# NextOne_R2.net
KiCad netlist of a schematic drawn in EAGLE
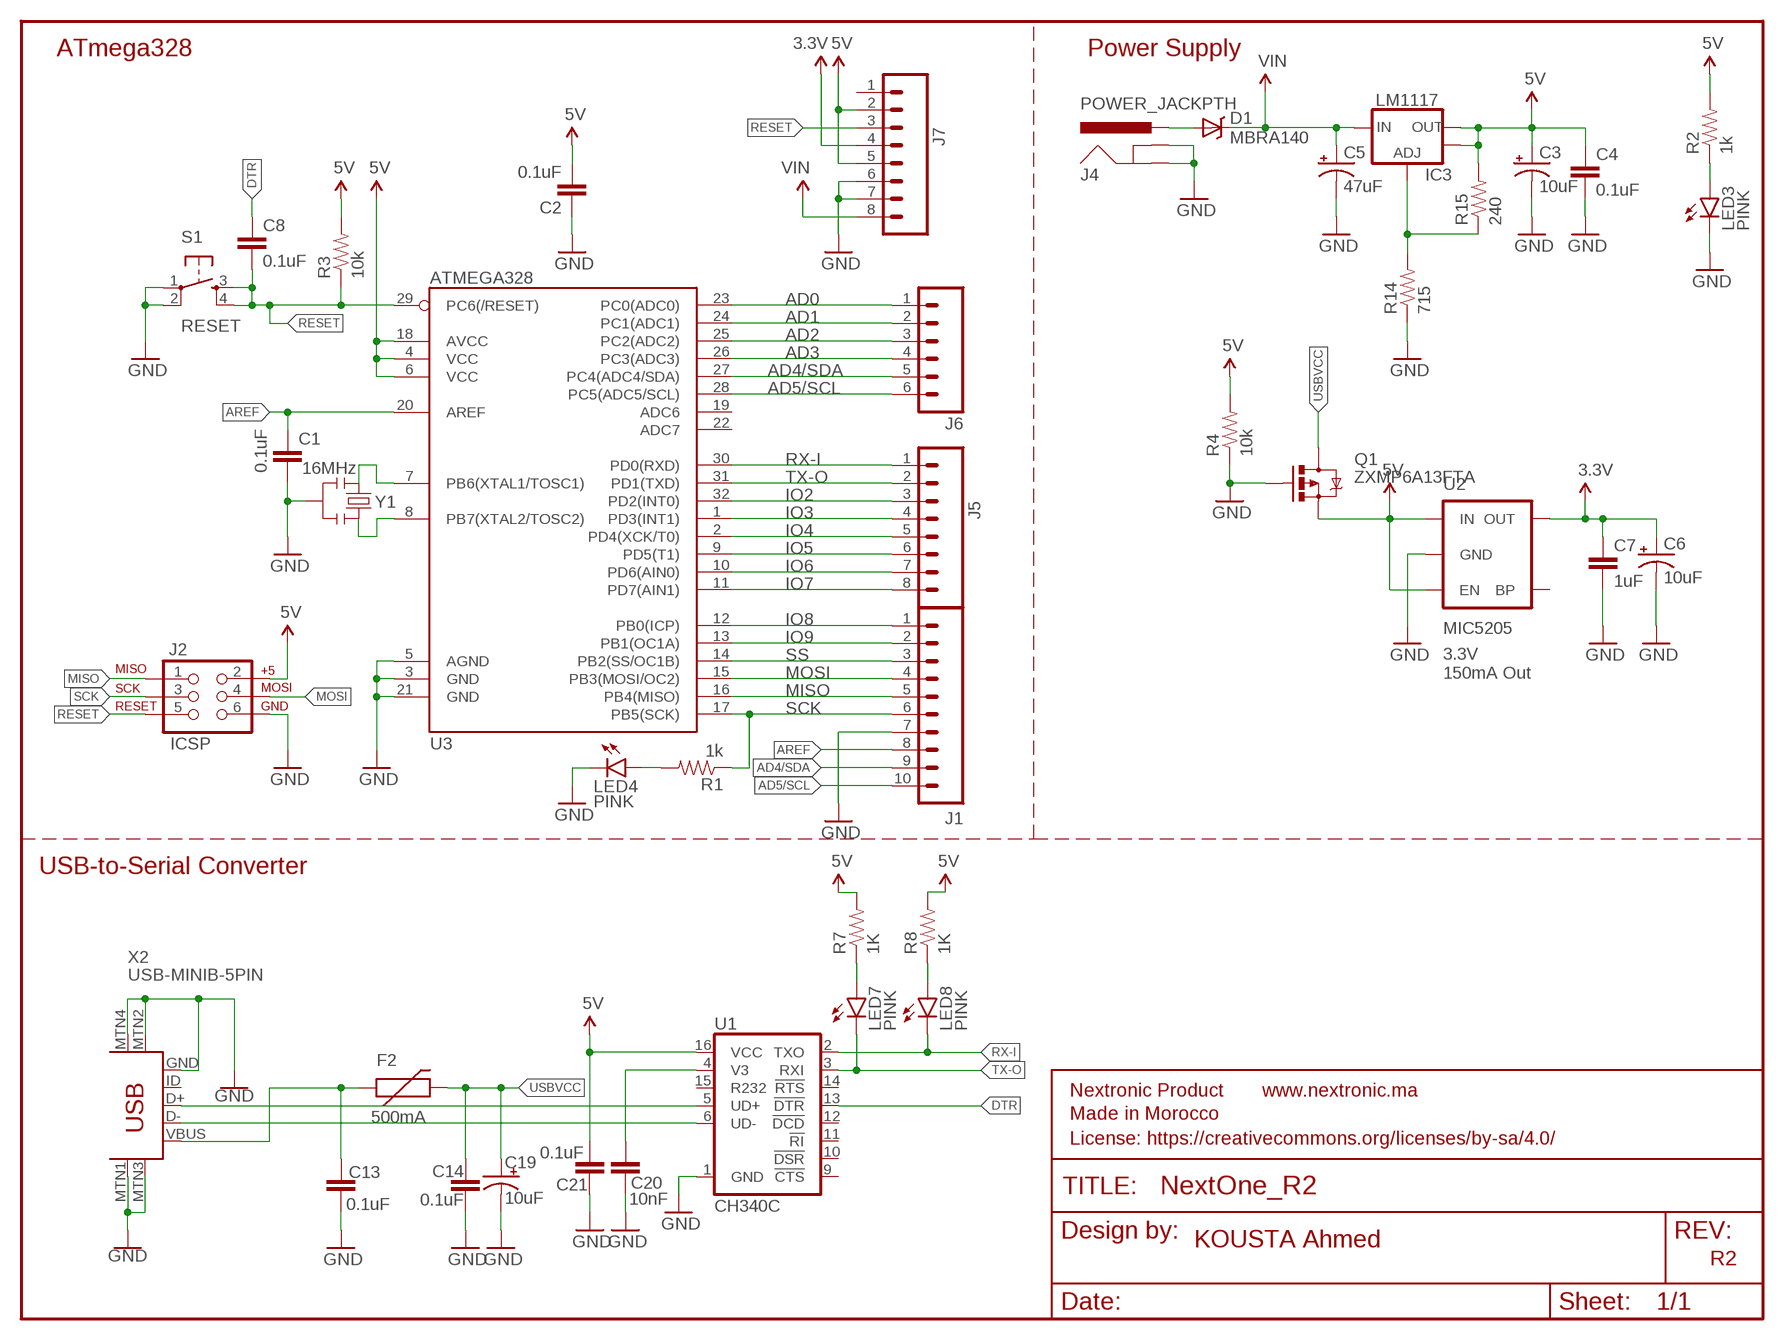
[diagram p0: schematic, sheet 1]

(export (version "E")
  (design (tool "Eeschema 10.0.6"))
  (components
    (comp (ref "C1")
      (value "0.1uF")
      (footprint "eagle-import:0603-CAP")
      (libsource (lib "eagle-import") (part "CAP0603-CAP"))
    )
    (comp (ref "C2")
      (value "0.1uF")
      (footprint "eagle-import:0603-CAP")
      (libsource (lib "eagle-import") (part "CAP0603-CAP"))
    )
    (comp (ref "C3")
      (value "10uF")
      (footprint "eagle-import:EIA3216")
      (libsource (lib "eagle-import") (part "CAP_POL1206"))
    )
    (comp (ref "C4")
      (value "0.1uF")
      (footprint "eagle-import:0603-CAP")
      (libsource (lib "eagle-import") (part "CAP0603-CAP"))
    )
    (comp (ref "C5")
      (value "47uF")
      (footprint "eagle-import:PANASONIC_D")
      (fields (field (name "MF") "PANASONIC ELECTRONIC COMPONENTS") (field (name "MPN") "EEE1CA470SP"))
      (libsource (lib "eagle-import") (part "CAP_POLD"))
    )
    (comp (ref "C6")
      (value "10uF")
      (footprint "eagle-import:EIA3216")
      (libsource (lib "eagle-import") (part "CAP_POL1206"))
    )
    (comp (ref "C7")
      (value "1uF")
      (footprint "eagle-import:0603-CAP")
      (fields (field (name "MF") "WALSIN") (field (name "MPN") "0805B104K500CT"))
      (libsource (lib "eagle-import") (part "CAP0603-CAP"))
    )
    (comp (ref "C8")
      (value "0.1uF")
      (footprint "eagle-import:0603-CAP")
      (libsource (lib "eagle-import") (part "CAP0603-CAP"))
    )
    (comp (ref "C13")
      (value "0.1uF")
      (footprint "eagle-import:0603")
      (libsource (lib "eagle-import") (part "0.1UF-0603-25V-(+80/-20%)"))
    )
    (comp (ref "C14")
      (value "0.1uF")
      (footprint "eagle-import:0603")
      (libsource (lib "eagle-import") (part "0.1UF-0603-25V-(+80/-20%)"))
    )
    (comp (ref "C19")
      (value "10uF")
      (footprint "eagle-import:EIA3216")
      (libsource (lib "eagle-import") (part "10UF-POLAR-EIA3216-16V-10%(TANT)"))
    )
    (comp (ref "C20")
      (value "10nF")
      (footprint "eagle-import:0603")
      (libsource (lib "eagle-import") (part "10NF-0603-50V-10%"))
    )
    (comp (ref "C21")
      (value "0.1uF")
      (footprint "eagle-import:0603")
      (libsource (lib "eagle-import") (part "0.1UF-0603-25V-(+80/-20%)"))
    )
    (comp (ref "D1")
      (value "MBRA140")
      (footprint "eagle-import:SMA-DIODE")
      (fields (field (name "MF") "DIODES INC.") (field (name "MPN") "B140-13-F"))
      (libsource (lib "eagle-import") (part "DIODE-SCHOTTKY_"))
    )
    (comp (ref "F2")
      (value "500mA")
      (footprint "eagle-import:PTC-1206")
      (libsource (lib "eagle-import") (part "PTCSMD"))
    )
    (comp (ref "FRAME1")
      (value "FRAME-LETTER")
      (footprint "eagle-import:CREATIVE_COMMONS")
      (fields (field (name "OC_FARNELL") "unknown"))
      (libsource (lib "eagle-import") (part "FRAME-LETTER"))
    )
    (comp (ref "IC3")
      (value "LM1117")
      (footprint "eagle-import:SOT223-ALT1")
      (fields (field (name "MF") "STMICROELECTRONICS") (field (name "MPN") "LD1117S33TR"))
      (libsource (lib "eagle-import") (part "V_REG_LM1117ALT1"))
    )
    (comp (ref "J1")
      (value "M10SILK_FEMALE_PTH")
      (footprint "eagle-import:1X10")
      (libsource (lib "eagle-import") (part "M10SILK_FEMALE_PTH"))
    )
    (comp (ref "J2")
      (value "ICSP")
      (footprint "eagle-import:2X3")
      (libsource (lib "eagle-import") (part "AVR_SPI_PRG_6PTH"))
    )
    (comp (ref "J4")
      (value "POWER_JACKPTH")
      (footprint "eagle-import:POWER_JACK_PTH")
      (libsource (lib "eagle-import") (part "POWER_JACKPTH"))
    )
    (comp (ref "J5")
      (value "M08")
      (footprint "eagle-import:1X08_ROUND")
      (libsource (lib "eagle-import") (part "M08"))
    )
    (comp (ref "J6")
      (value "M06SILK_FEMALE_PTH")
      (footprint "eagle-import:1X06")
      (libsource (lib "eagle-import") (part "M06SILK_FEMALE_PTH"))
    )
    (comp (ref "J7")
      (value "M08")
      (footprint "eagle-import:1X08_ROUND")
      (libsource (lib "eagle-import") (part "M08"))
    )
    (comp (ref "LED3")
      (value "PINK")
      (footprint "eagle-import:LED-1206@1")
      (libsource (lib "eagle-import") (part "LED-PINK1206"))
    )
    (comp (ref "LED4")
      (value "PINK")
      (footprint "eagle-import:LED-1206@1")
      (libsource (lib "eagle-import") (part "LED-PINK1206"))
    )
    (comp (ref "LED7")
      (value "PINK")
      (footprint "eagle-import:LED-1206@1")
      (libsource (lib "eagle-import") (part "LED-PINK1206"))
    )
    (comp (ref "LED8")
      (value "PINK")
      (footprint "eagle-import:LED-1206@1")
      (libsource (lib "eagle-import") (part "LED-PINK1206"))
    )
    (comp (ref "Q1")
      (value "ZXMP6A13FTA")
      (footprint "eagle-import:SOT23-3")
      (fields (field (name "MF") "DIODES INC."))
      (libsource (lib "eagle-import") (part "MOSFET-PCHANNELSMD"))
    )
    (comp (ref "R1")
      (value "1k")
      (footprint "eagle-import:0603-RES")
      (libsource (lib "eagle-import") (part "RESISTOR0603-RES"))
    )
    (comp (ref "R2")
      (value "1k")
      (footprint "eagle-import:0603-RES")
      (libsource (lib "eagle-import") (part "RESISTOR0603-RES"))
    )
    (comp (ref "R3")
      (value "10k")
      (footprint "eagle-import:0603-RES")
      (libsource (lib "eagle-import") (part "RESISTOR0603-RES"))
    )
    (comp (ref "R4")
      (value "10k")
      (footprint "eagle-import:0603-RES")
      (libsource (lib "eagle-import") (part "RESISTOR0603-RES"))
    )
    (comp (ref "R7")
      (value "1K")
      (footprint "eagle-import:0603-RES")
      (fields (field (name "MF") "VISHAY/DALE") (field (name "MPN") "CRCW25121K00JNEG"))
      (libsource (lib "eagle-import") (part "1KOHM-1/10W-1%(0603)"))
    )
    (comp (ref "R8")
      (value "1K")
      (footprint "eagle-import:0603-RES")
      (fields (field (name "MF") "VISHAY/DALE") (field (name "MPN") "CRCW25121K00JNEG"))
      (libsource (lib "eagle-import") (part "1KOHM-1/10W-1%(0603)"))
    )
    (comp (ref "R14")
      (value "715")
      (footprint "eagle-import:0603-RES")
      (libsource (lib "eagle-import") (part "RESISTOR0603-RES"))
    )
    (comp (ref "R15")
      (value "240")
      (footprint "eagle-import:0603-RES")
      (libsource (lib "eagle-import") (part "RESISTOR0603-RES"))
    )
    (comp (ref "S1")
      (value "RESET")
      (footprint "eagle-import:TACTILE_SWITCH_SMD")
      (libsource (lib "eagle-import") (part "TAC_SWITCHSMD"))
    )
    (comp (ref "U1")
      (value "CH340C")
      (footprint "eagle-import:SO016")
      (libsource (lib "eagle-import") (part "CH340C"))
    )
    (comp (ref "U2")
      (value "MIC5205")
      (footprint "eagle-import:SOT23-5")
      (libsource (lib "eagle-import") (part "V_REG_LDOSMD"))
    )
    (comp (ref "U3")
      (value "ATMEGA328")
      (footprint "eagle-import:TQFP32-08")
      (fields (field (name "MF") "ATMEL") (field (name "MPN") "ATMEGA328P-AN"))
      (libsource (lib "eagle-import") (part "ATMEGA168"))
    )
    (comp (ref "X2")
      (value "USB-MINIB-5PIN")
      (footprint "eagle-import:USB-MINIB")
      (libsource (lib "eagle-import") (part "USB-MINIB-5PIN"))
    )
    (comp (ref "Y1")
      (value "16MHz")
      (footprint "eagle-import:RESONATOR-SMD")
      (libsource (lib "eagle-import") (part "RESONATORSMD"))
    )
  )
  (nets
    (net (code "1") (name "/AD0") (class "Default")
      (node (ref "J6") (pin "1") (pinfunction "1_1") (pintype "passive"))
      (node (ref "U3") (pin "23") (pinfunction "PC0(ADC0)_23") (pintype "bidirectional"))
    )
    (net (code "2") (name "/AD1") (class "Default")
      (node (ref "J6") (pin "2") (pinfunction "2_2") (pintype "passive"))
      (node (ref "U3") (pin "24") (pinfunction "PC1(ADC1)_24") (pintype "bidirectional"))
    )
    (net (code "3") (name "/AD2") (class "Default")
      (node (ref "J6") (pin "3") (pinfunction "3_3") (pintype "passive"))
      (node (ref "U3") (pin "25") (pinfunction "PC2(ADC2)_25") (pintype "bidirectional"))
    )
    (net (code "4") (name "/AD3") (class "Default")
      (node (ref "J6") (pin "4") (pinfunction "4_4") (pintype "passive"))
      (node (ref "U3") (pin "26") (pinfunction "PC3(ADC3)_26") (pintype "bidirectional"))
    )
    (net (code "5") (name "/IO2") (class "Default")
      (node (ref "J5") (pin "3") (pinfunction "3_3") (pintype "passive"))
      (node (ref "U3") (pin "32") (pinfunction "PD2(INT0)_32") (pintype "bidirectional"))
    )
    (net (code "6") (name "/IO3") (class "Default")
      (node (ref "J5") (pin "4") (pinfunction "4_4") (pintype "passive"))
      (node (ref "U3") (pin "1") (pinfunction "PD3(INT1)_1") (pintype "bidirectional"))
    )
    (net (code "7") (name "/IO4") (class "Default")
      (node (ref "J5") (pin "5") (pinfunction "5_5") (pintype "passive"))
      (node (ref "U3") (pin "2") (pinfunction "PD4(XCK/T0)_2") (pintype "bidirectional"))
    )
    (net (code "8") (name "/IO5") (class "Default")
      (node (ref "J5") (pin "6") (pinfunction "6_6") (pintype "passive"))
      (node (ref "U3") (pin "9") (pinfunction "PD5(T1)_9") (pintype "bidirectional"))
    )
    (net (code "9") (name "/IO6") (class "Default")
      (node (ref "J5") (pin "7") (pinfunction "7_7") (pintype "passive"))
      (node (ref "U3") (pin "10") (pinfunction "PD6(AIN0)_10") (pintype "bidirectional"))
    )
    (net (code "10") (name "/IO7") (class "Default")
      (node (ref "J5") (pin "8") (pinfunction "8_8") (pintype "passive"))
      (node (ref "U3") (pin "11") (pinfunction "PD7(AIN1)_11") (pintype "bidirectional"))
    )
    (net (code "11") (name "/IO8") (class "Default")
      (node (ref "J1") (pin "1") (pinfunction "1_1") (pintype "passive"))
      (node (ref "U3") (pin "12") (pinfunction "PB0(ICP)_12") (pintype "bidirectional"))
    )
    (net (code "12") (name "/IO9") (class "Default")
      (node (ref "J1") (pin "2") (pinfunction "2_2") (pintype "passive"))
      (node (ref "U3") (pin "13") (pinfunction "PB1(OC1A)_13") (pintype "bidirectional"))
    )
    (net (code "13") (name "/SS") (class "Default")
      (node (ref "J1") (pin "3") (pinfunction "3_3") (pintype "passive"))
      (node (ref "U3") (pin "14") (pinfunction "PB2(SS/OC1B)_14") (pintype "bidirectional"))
    )
    (net (code "14") (name "3.3V") (class "Default")
      (node (ref "C6") (pin "A") (pinfunction "+_A") (pintype "passive"))
      (node (ref "C7") (pin "1") (pinfunction "1_1") (pintype "passive"))
      (node (ref "J7") (pin "4") (pinfunction "4_4") (pintype "passive"))
      (node (ref "U2") (pin "5") (pinfunction "OUT_5") (pintype "passive"))
    )
    (net (code "15") (name "5V") (class "Default")
      (node (ref "C2") (pin "2") (pinfunction "2_2") (pintype "passive"))
      (node (ref "C21") (pin "1") (pinfunction "1_1") (pintype "passive"))
      (node (ref "C3") (pin "A") (pinfunction "+_A") (pintype "passive"))
      (node (ref "C4") (pin "1") (pinfunction "1_1") (pintype "passive"))
      (node (ref "IC3") (pin "2") (pinfunction "OUT_2") (pintype "output"))
      (node (ref "IC3") (pin "4") (pinfunction "OUT_4") (pintype "output"))
      (node (ref "J2") (pin "2") (pinfunction "2_2") (pintype "passive"))
      (node (ref "J7") (pin "2") (pinfunction "2_2") (pintype "passive"))
      (node (ref "J7") (pin "5") (pinfunction "5_5") (pintype "passive"))
      (node (ref "Q1") (pin "2") (pinfunction "S_2") (pintype "passive"))
      (node (ref "R15") (pin "2") (pinfunction "2_2") (pintype "passive"))
      (node (ref "R2") (pin "2") (pinfunction "2_2") (pintype "passive"))
      (node (ref "R3") (pin "2") (pinfunction "2_2") (pintype "passive"))
      (node (ref "R4") (pin "2") (pinfunction "2_2") (pintype "passive"))
      (node (ref "R7") (pin "2") (pinfunction "2_2") (pintype "passive"))
      (node (ref "R8") (pin "2") (pinfunction "2_2") (pintype "passive"))
      (node (ref "U1") (pin "16") (pinfunction "VCC_16") (pintype "bidirectional"))
      (node (ref "U2") (pin "1") (pinfunction "IN_1") (pintype "input"))
      (node (ref "U2") (pin "3") (pinfunction "EN_3") (pintype "input"))
      (node (ref "U3") (pin "18") (pinfunction "AVCC_18") (pintype "bidirectional"))
      (node (ref "U3") (pin "4") (pinfunction "VCC_4") (pintype "bidirectional"))
      (node (ref "U3") (pin "6") (pinfunction "VCC_6") (pintype "bidirectional"))
    )
    (net (code "16") (name "AD4{slash}SDA") (class "Default")
      (node (ref "J1") (pin "9") (pinfunction "9_9") (pintype "passive"))
      (node (ref "J6") (pin "5") (pinfunction "5_5") (pintype "passive"))
      (node (ref "U3") (pin "27") (pinfunction "PC4(ADC4/SDA)_27") (pintype "bidirectional"))
    )
    (net (code "17") (name "AD5{slash}SCL") (class "Default")
      (node (ref "J1") (pin "10") (pinfunction "10_10") (pintype "passive"))
      (node (ref "J6") (pin "6") (pinfunction "6_6") (pintype "passive"))
      (node (ref "U3") (pin "28") (pinfunction "PC5(ADC5/SCL)_28") (pintype "bidirectional"))
    )
    (net (code "18") (name "AREF") (class "Default")
      (node (ref "C1") (pin "1") (pinfunction "1_1") (pintype "passive"))
      (node (ref "J1") (pin "8") (pinfunction "8_8") (pintype "passive"))
      (node (ref "U3") (pin "20") (pinfunction "AREF_20") (pintype "bidirectional"))
    )
    (net (code "19") (name "DTR") (class "Default")
      (node (ref "C8") (pin "1") (pinfunction "1_1") (pintype "passive"))
      (node (ref "U1") (pin "13") (pinfunction "~{DTR}_13") (pintype "bidirectional"))
    )
    (net (code "20") (name "GND") (class "Default")
      (node (ref "C1") (pin "2") (pinfunction "2_2") (pintype "passive"))
      (node (ref "C13") (pin "2") (pinfunction "2_2") (pintype "passive"))
      (node (ref "C14") (pin "2") (pinfunction "2_2") (pintype "passive"))
      (node (ref "C19") (pin "-") (pinfunction "-_-") (pintype "passive"))
      (node (ref "C2") (pin "1") (pinfunction "1_1") (pintype "passive"))
      (node (ref "C20") (pin "2") (pinfunction "2_2") (pintype "passive"))
      (node (ref "C21") (pin "2") (pinfunction "2_2") (pintype "passive"))
      (node (ref "C3") (pin "C") (pinfunction "-_C") (pintype "passive"))
      (node (ref "C4") (pin "2") (pinfunction "2_2") (pintype "passive"))
      (node (ref "C5") (pin "-") (pinfunction "-_-") (pintype "passive"))
      (node (ref "C6") (pin "C") (pinfunction "-_C") (pintype "passive"))
      (node (ref "C7") (pin "2") (pinfunction "2_2") (pintype "passive"))
      (node (ref "J1") (pin "7") (pinfunction "7_7") (pintype "passive"))
      (node (ref "J2") (pin "6") (pinfunction "6_6") (pintype "passive"))
      (node (ref "J4") (pin "GND") (pinfunction "GND_GND") (pintype "bidirectional"))
      (node (ref "J4") (pin "GNDBREAK") (pinfunction "GNDBREAK_GNDBREAK") (pintype "bidirectional"))
      (node (ref "J7") (pin "6") (pinfunction "6_6") (pintype "passive"))
      (node (ref "J7") (pin "7") (pinfunction "7_7") (pintype "passive"))
      (node (ref "LED3") (pin "C") (pinfunction "C_C") (pintype "passive"))
      (node (ref "LED4") (pin "C") (pinfunction "C_C") (pintype "passive"))
      (node (ref "Q1") (pin "1") (pinfunction "G_1") (pintype "passive"))
      (node (ref "R14") (pin "1") (pinfunction "1_1") (pintype "passive"))
      (node (ref "R4") (pin "1") (pinfunction "1_1") (pintype "passive"))
      (node (ref "S1") (pin "1") (pinfunction "1_1") (pintype "passive"))
      (node (ref "S1") (pin "2") (pinfunction "2_2") (pintype "passive"))
      (node (ref "U1") (pin "1") (pinfunction "GND_1") (pintype "bidirectional"))
      (node (ref "U2") (pin "2") (pinfunction "GND_2") (pintype "input"))
      (node (ref "U3") (pin "21") (pinfunction "GND_21") (pintype "bidirectional"))
      (node (ref "U3") (pin "3") (pinfunction "GND_3") (pintype "bidirectional"))
      (node (ref "U3") (pin "5") (pinfunction "AGND_5") (pintype "bidirectional"))
      (node (ref "X2") (pin "GND") (pinfunction "GND_GND") (pintype "bidirectional"))
      (node (ref "X2") (pin "MTN1") (pinfunction "MTN2_MTN1") (pintype "bidirectional"))
      (node (ref "X2") (pin "MTN2") (pinfunction "MTN3_MTN2") (pintype "bidirectional"))
      (node (ref "X2") (pin "MTN3") (pinfunction "MTN1_MTN3") (pintype "bidirectional"))
      (node (ref "X2") (pin "MTN4") (pinfunction "MTN4_MTN4") (pintype "bidirectional"))
      (node (ref "Y1") (pin "2") (pinfunction "2_2") (pintype "passive"))
    )
    (net (code "21") (name "MISO") (class "Default")
      (node (ref "J1") (pin "5") (pinfunction "5_5") (pintype "passive"))
      (node (ref "J2") (pin "1") (pinfunction "1_1") (pintype "passive"))
      (node (ref "U3") (pin "16") (pinfunction "PB4(MISO)_16") (pintype "bidirectional"))
    )
    (net (code "22") (name "MOSI") (class "Default")
      (node (ref "J1") (pin "4") (pinfunction "4_4") (pintype "passive"))
      (node (ref "J2") (pin "4") (pinfunction "4_4") (pintype "passive"))
      (node (ref "U3") (pin "15") (pinfunction "PB3(MOSI/OC2)_15") (pintype "bidirectional"))
    )
    (net (code "23") (name "Net-(C13-Pad1)") (class "Default")
      (node (ref "C13") (pin "1") (pinfunction "1_1") (pintype "passive"))
      (node (ref "F2") (pin "1") (pinfunction "1_1") (pintype "bidirectional"))
      (node (ref "X2") (pin "VBUS") (pinfunction "VBUS_VBUS") (pintype "bidirectional"))
    )
    (net (code "24") (name "Net-(D1-PadA)") (class "Default")
      (node (ref "D1") (pin "A") (pinfunction "A_A") (pintype "passive"))
      (node (ref "J4") (pin "PWR") (pinfunction "PWR_PWR") (pintype "bidirectional"))
    )
    (net (code "25") (name "Net-(IC3-ADJ)") (class "Default")
      (node (ref "IC3") (pin "1") (pinfunction "ADJ_1") (pintype "input"))
      (node (ref "R14") (pin "2") (pinfunction "2_2") (pintype "passive"))
      (node (ref "R15") (pin "1") (pinfunction "1_1") (pintype "passive"))
    )
    (net (code "26") (name "Net-(LED3-PadA)") (class "Default")
      (node (ref "LED3") (pin "A") (pinfunction "A_A") (pintype "passive"))
      (node (ref "R2") (pin "1") (pinfunction "1_1") (pintype "passive"))
    )
    (net (code "27") (name "Net-(LED4-PadA)") (class "Default")
      (node (ref "LED4") (pin "A") (pinfunction "A_A") (pintype "passive"))
      (node (ref "R1") (pin "2") (pinfunction "2_2") (pintype "passive"))
    )
    (net (code "28") (name "Net-(LED7-PadA)") (class "Default")
      (node (ref "LED7") (pin "A") (pinfunction "A_A") (pintype "passive"))
      (node (ref "R7") (pin "1") (pinfunction "1_1") (pintype "passive"))
    )
    (net (code "29") (name "Net-(LED8-PadA)") (class "Default")
      (node (ref "LED8") (pin "A") (pinfunction "A_A") (pintype "passive"))
      (node (ref "R8") (pin "1") (pinfunction "1_1") (pintype "passive"))
    )
    (net (code "30") (name "Net-(U1-UD+)") (class "Default")
      (node (ref "U1") (pin "5") (pinfunction "UD+_5") (pintype "bidirectional"))
      (node (ref "X2") (pin "D+") (pinfunction "D+_D+") (pintype "bidirectional"))
    )
    (net (code "31") (name "Net-(U1-UD-)") (class "Default")
      (node (ref "U1") (pin "6") (pinfunction "UD-_6") (pintype "bidirectional"))
      (node (ref "X2") (pin "D-") (pinfunction "D-_D-") (pintype "bidirectional"))
    )
    (net (code "32") (name "Net-(U1-V3)") (class "Default")
      (node (ref "C20") (pin "1") (pinfunction "1_1") (pintype "passive"))
      (node (ref "U1") (pin "4") (pinfunction "V3_4") (pintype "bidirectional"))
    )
    (net (code "33") (name "Net-(U3-PB6(XTAL1{slash}TOSC1))") (class "Default")
      (node (ref "U3") (pin "7") (pinfunction "PB6(XTAL1/TOSC1)_7") (pintype "bidirectional"))
      (node (ref "Y1") (pin "1") (pinfunction "1_1") (pintype "passive"))
    )
    (net (code "34") (name "Net-(U3-PB7(XTAL2{slash}TOSC2))") (class "Default")
      (node (ref "U3") (pin "8") (pinfunction "PB7(XTAL2/TOSC2)_8") (pintype "bidirectional"))
      (node (ref "Y1") (pin "3") (pinfunction "3_3") (pintype "passive"))
    )
    (net (code "35") (name "RESET") (class "Default")
      (node (ref "C8") (pin "2") (pinfunction "2_2") (pintype "passive"))
      (node (ref "J2") (pin "5") (pinfunction "5_5") (pintype "passive"))
      (node (ref "J7") (pin "3") (pinfunction "3_3") (pintype "passive"))
      (node (ref "R3") (pin "1") (pinfunction "1_1") (pintype "passive"))
      (node (ref "S1") (pin "3") (pinfunction "3_3") (pintype "passive"))
      (node (ref "S1") (pin "4") (pinfunction "4_4") (pintype "passive"))
      (node (ref "U3") (pin "29") (pinfunction "PC6(/RESET)_29") (pintype "bidirectional"))
    )
    (net (code "36") (name "RX-I") (class "Default")
      (node (ref "J5") (pin "1") (pinfunction "1_1") (pintype "passive"))
      (node (ref "LED8") (pin "C") (pinfunction "C_C") (pintype "passive"))
      (node (ref "U1") (pin "2") (pinfunction "TXO_2") (pintype "bidirectional"))
      (node (ref "U3") (pin "30") (pinfunction "PD0(RXD)_30") (pintype "bidirectional"))
    )
    (net (code "37") (name "SCK") (class "Default")
      (node (ref "J1") (pin "6") (pinfunction "6_6") (pintype "passive"))
      (node (ref "J2") (pin "3") (pinfunction "3_3") (pintype "passive"))
      (node (ref "R1") (pin "1") (pinfunction "1_1") (pintype "passive"))
      (node (ref "U3") (pin "17") (pinfunction "PB5(SCK)_17") (pintype "bidirectional"))
    )
    (net (code "38") (name "TX-O") (class "Default")
      (node (ref "J5") (pin "2") (pinfunction "2_2") (pintype "passive"))
      (node (ref "LED7") (pin "C") (pinfunction "C_C") (pintype "passive"))
      (node (ref "U1") (pin "3") (pinfunction "RXI_3") (pintype "bidirectional"))
      (node (ref "U3") (pin "31") (pinfunction "PD1(TXD)_31") (pintype "bidirectional"))
    )
    (net (code "39") (name "USBVCC") (class "Default")
      (node (ref "C14") (pin "1") (pinfunction "1_1") (pintype "passive"))
      (node (ref "C19") (pin "+") (pinfunction "+_+") (pintype "passive"))
      (node (ref "F2") (pin "2") (pinfunction "2_2") (pintype "bidirectional"))
      (node (ref "Q1") (pin "3") (pinfunction "D_3") (pintype "passive"))
    )
    (net (code "40") (name "VIN") (class "Default")
      (node (ref "C5") (pin "+") (pinfunction "+_+") (pintype "passive"))
      (node (ref "D1") (pin "C") (pinfunction "C_C") (pintype "passive"))
      (node (ref "IC3") (pin "3") (pinfunction "IN_3") (pintype "input"))
      (node (ref "J7") (pin "8") (pinfunction "8_8") (pintype "passive"))
    )
    (net (code "41") (name "unconnected-(J7-Pad1)") (class "Default")
      (node (ref "J7") (pin "1") (pinfunction "1_1") (pintype "passive"))
    )
    (net (code "42") (name "unconnected-(U1-R232-Pad15)") (class "Default")
      (node (ref "U1") (pin "15") (pinfunction "R232_15") (pintype "bidirectional"))
    )
    (net (code "43") (name "unconnected-(U1-~{CTS}-Pad9)") (class "Default")
      (node (ref "U1") (pin "9") (pinfunction "~{CTS}_9") (pintype "bidirectional"))
    )
    (net (code "44") (name "unconnected-(U1-~{DCD}-Pad12)") (class "Default")
      (node (ref "U1") (pin "12") (pinfunction "~{DCD}_12") (pintype "bidirectional"))
    )
    (net (code "45") (name "unconnected-(U1-~{DSR}-Pad10)") (class "Default")
      (node (ref "U1") (pin "10") (pinfunction "~{DSR}_10") (pintype "bidirectional"))
    )
    (net (code "46") (name "unconnected-(U1-~{RI}-Pad11)") (class "Default")
      (node (ref "U1") (pin "11") (pinfunction "~{RI}_11") (pintype "bidirectional"))
    )
    (net (code "47") (name "unconnected-(U1-~{RTS}-Pad14)") (class "Default")
      (node (ref "U1") (pin "14") (pinfunction "~{RTS}_14") (pintype "bidirectional"))
    )
    (net (code "48") (name "unconnected-(U2-BP-Pad4)") (class "Default")
      (node (ref "U2") (pin "4") (pinfunction "BP_4") (pintype "input"))
    )
    (net (code "49") (name "unconnected-(U3-ADC6-Pad19)") (class "Default")
      (node (ref "U3") (pin "19") (pinfunction "ADC6_19") (pintype "bidirectional"))
    )
    (net (code "50") (name "unconnected-(U3-ADC7-Pad22)") (class "Default")
      (node (ref "U3") (pin "22") (pinfunction "ADC7_22") (pintype "bidirectional"))
    )
    (net (code "51") (name "unconnected-(X2-PadID)") (class "Default")
      (node (ref "X2") (pin "ID") (pinfunction "ID_ID") (pintype "bidirectional"))
    )
  )
)
